# toshiba_board.net
KiCad netlist of a schematic drawn in EAGLE
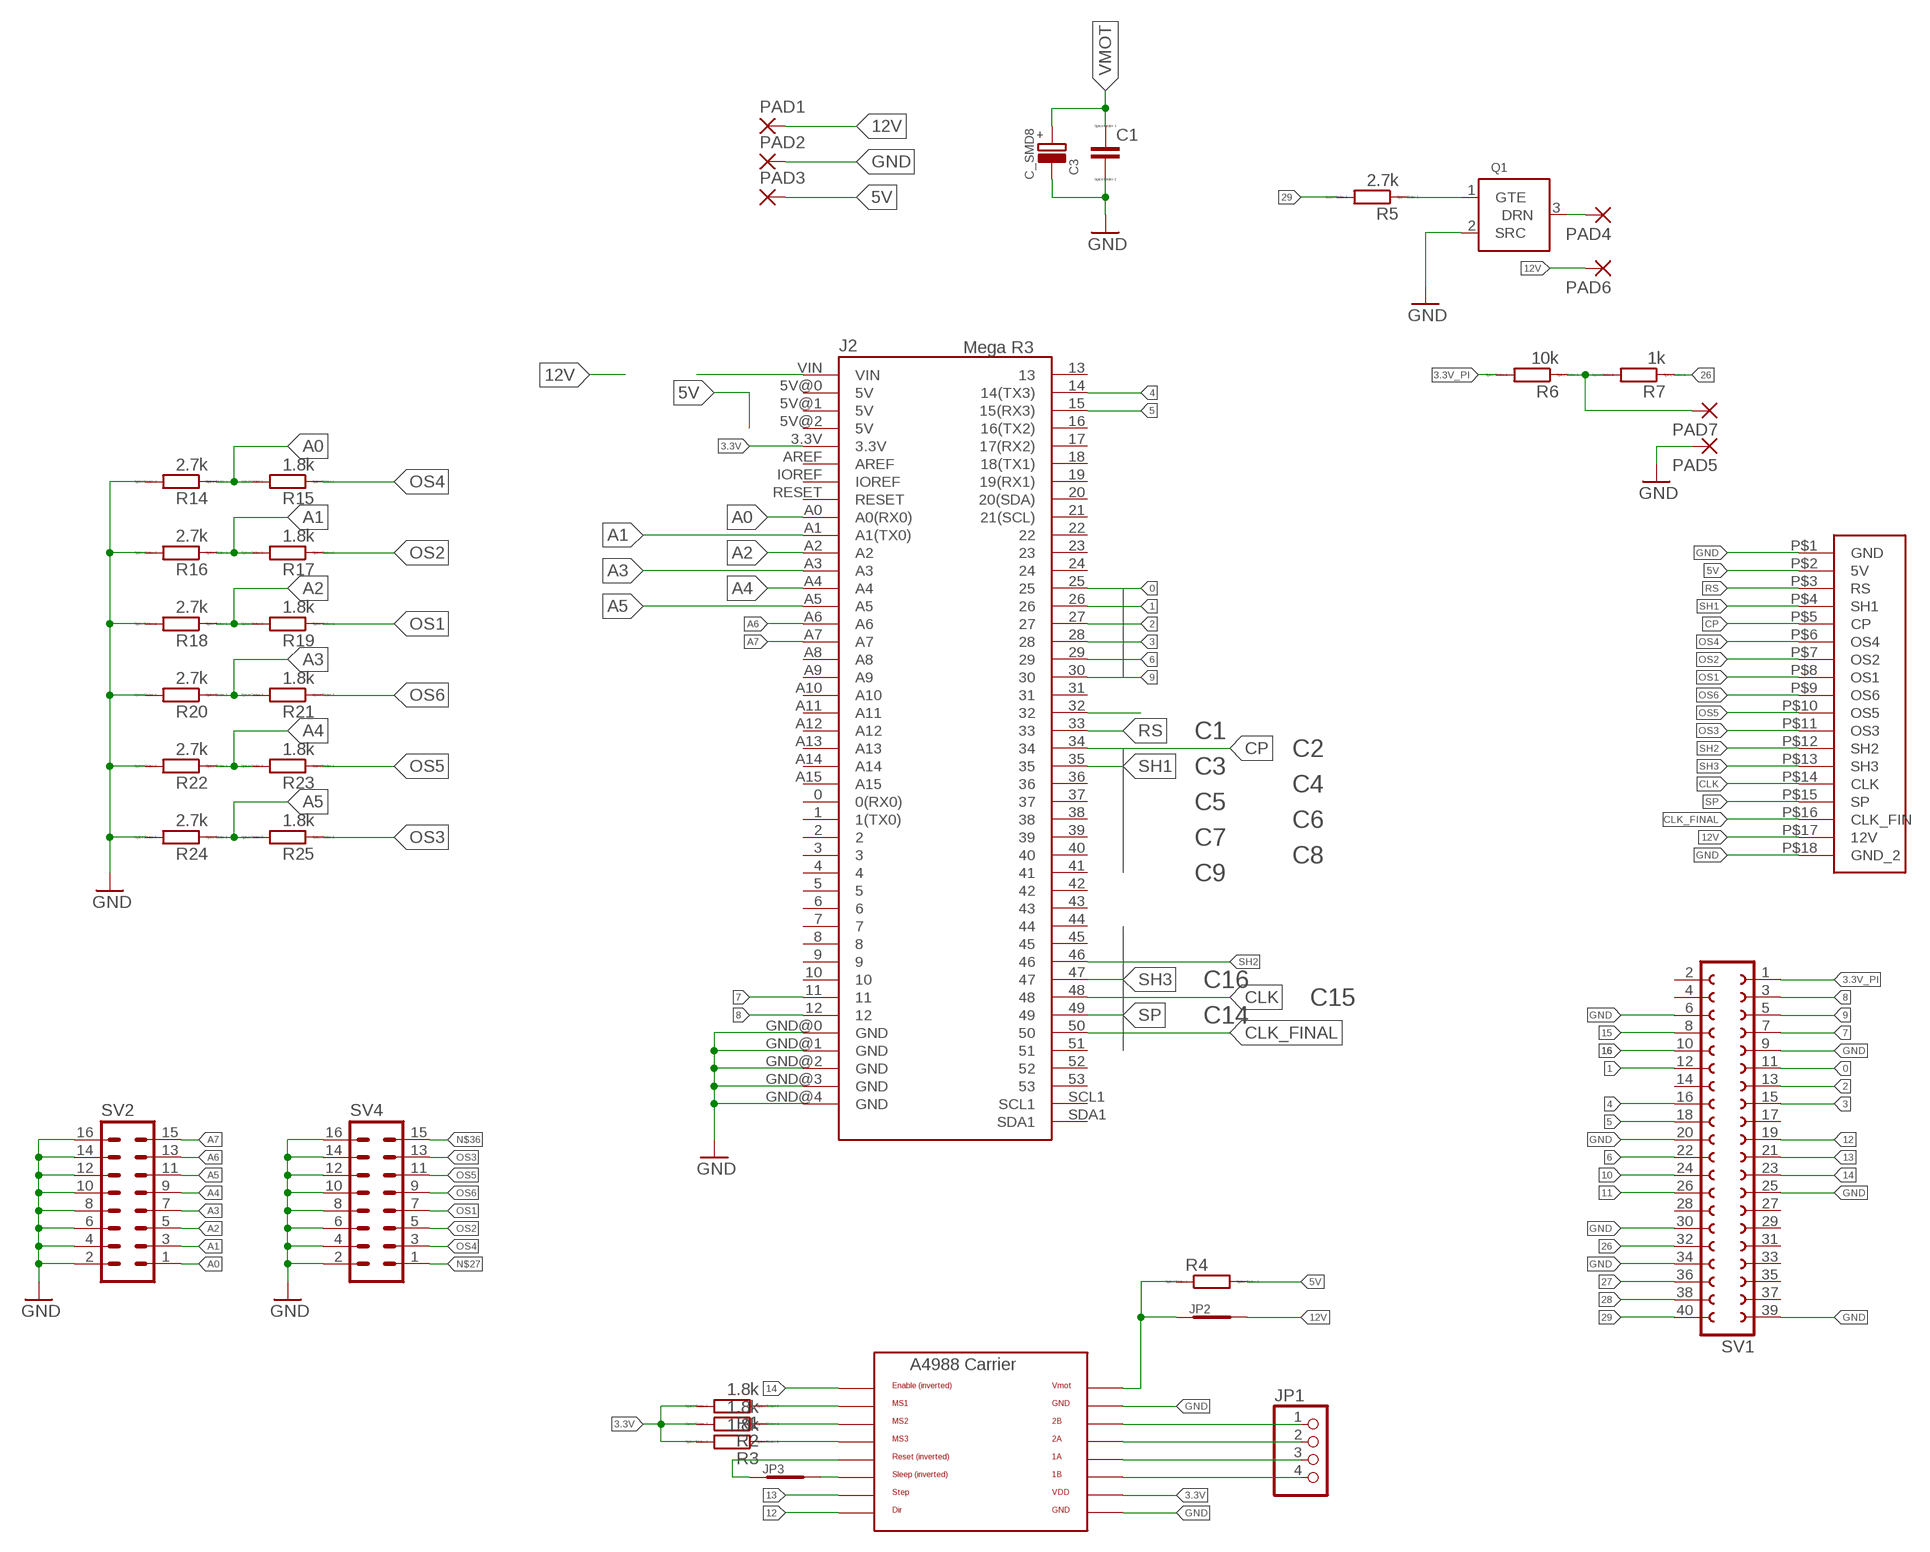
[diagram p0: schematic, sheet 1]

(export (version "E")
  (design (tool "Eeschema 10.0.6"))
  (components
    (comp (ref "C1")
      (value "C-EUC0805")
      (footprint "eagle-import:C0805")
      (libsource (lib "eagle-import") (part "C-EUC0805"))
    )
    (comp (ref "C3")
      (value "C_SMD8")
      (footprint "eagle-import:C-SMD-8MM")
      (libsource (lib "eagle-import") (part "C_SMD8"))
    )
    (comp (ref "J2")
      (value "Mega R3")
      (footprint "eagle-import:ARDUINO_MEGA")
      (libsource (lib "eagle-import") (part "ARDUINO-MEGAFULL"))
    )
    (comp (ref "JP1")
      (value "PINHD-1X4")
      (footprint "eagle-import:1X04")
      (libsource (lib "eagle-import") (part "PINHD-1X4"))
    )
    (comp (ref "JP2")
      (value "SHORT0805")
      (footprint "eagle-import:0805_SHORT")
      (libsource (lib "eagle-import") (part "SHORT0805"))
    )
    (comp (ref "JP3")
      (value "SHORT0805")
      (footprint "eagle-import:0805_SHORT")
      (libsource (lib "eagle-import") (part "SHORT0805"))
    )
    (comp (ref "PAD1")
      (value "SMD2")
      (footprint "eagle-import:SMD1,27-2,54")
      (libsource (lib "eagle-import") (part "SMD2"))
    )
    (comp (ref "PAD2")
      (value "SMD2")
      (footprint "eagle-import:SMD1,27-2,54")
      (libsource (lib "eagle-import") (part "SMD2"))
    )
    (comp (ref "PAD3")
      (value "SMD2")
      (footprint "eagle-import:SMD1,27-2,54")
      (libsource (lib "eagle-import") (part "SMD2"))
    )
    (comp (ref "PAD4")
      (value "SMD2")
      (footprint "eagle-import:SMD1,27-2,54")
      (libsource (lib "eagle-import") (part "SMD2"))
    )
    (comp (ref "PAD5")
      (value "SMD2")
      (footprint "eagle-import:SMD1,27-2,54")
      (libsource (lib "eagle-import") (part "SMD2"))
    )
    (comp (ref "PAD6")
      (value "SMD2")
      (footprint "eagle-import:SMD1,27-2,54")
      (libsource (lib "eagle-import") (part "SMD2"))
    )
    (comp (ref "PAD7")
      (value "SMD2")
      (footprint "eagle-import:SMD1,27-2,54")
      (libsource (lib "eagle-import") (part "SMD2"))
    )
    (comp (ref "Q1")
      (value "BSS138")
      (footprint "eagle-import:SOT23")
      (libsource (lib "eagle-import") (part "BSS138"))
    )
    (comp (ref "R1")
      (value "1.8k")
      (footprint "eagle-import:R0603")
      (libsource (lib "eagle-import") (part "R-EU_R0603"))
    )
    (comp (ref "R2")
      (value "1.8k")
      (footprint "eagle-import:R0603")
      (libsource (lib "eagle-import") (part "R-EU_R0603"))
    )
    (comp (ref "R3")
      (value "1.8k")
      (footprint "eagle-import:R0603")
      (libsource (lib "eagle-import") (part "R-EU_R0603"))
    )
    (comp (ref "R4")
      (value "R-EU_R0805")
      (footprint "eagle-import:R0805")
      (libsource (lib "eagle-import") (part "R-EU_R0805"))
    )
    (comp (ref "R5")
      (value "2.7k")
      (footprint "eagle-import:R0603")
      (libsource (lib "eagle-import") (part "R-EU_R0603"))
    )
    (comp (ref "R6")
      (value "10k")
      (footprint "eagle-import:R0603")
      (libsource (lib "eagle-import") (part "R-EU_R0603"))
    )
    (comp (ref "R7")
      (value "1k")
      (footprint "eagle-import:R0603")
      (libsource (lib "eagle-import") (part "R-EU_R0603"))
    )
    (comp (ref "R14")
      (value "2.7k")
      (footprint "eagle-import:R0603")
      (libsource (lib "eagle-import") (part "R-EU_R0603"))
    )
    (comp (ref "R15")
      (value "1.8k")
      (footprint "eagle-import:R0603")
      (libsource (lib "eagle-import") (part "R-EU_R0603"))
    )
    (comp (ref "R16")
      (value "2.7k")
      (footprint "eagle-import:R0603")
      (libsource (lib "eagle-import") (part "R-EU_R0603"))
    )
    (comp (ref "R17")
      (value "1.8k")
      (footprint "eagle-import:R0603")
      (libsource (lib "eagle-import") (part "R-EU_R0603"))
    )
    (comp (ref "R18")
      (value "2.7k")
      (footprint "eagle-import:R0603")
      (libsource (lib "eagle-import") (part "R-EU_R0603"))
    )
    (comp (ref "R19")
      (value "1.8k")
      (footprint "eagle-import:R0603")
      (libsource (lib "eagle-import") (part "R-EU_R0603"))
    )
    (comp (ref "R20")
      (value "2.7k")
      (footprint "eagle-import:R0603")
      (libsource (lib "eagle-import") (part "R-EU_R0603"))
    )
    (comp (ref "R21")
      (value "1.8k")
      (footprint "eagle-import:R0603")
      (libsource (lib "eagle-import") (part "R-EU_R0603"))
    )
    (comp (ref "R22")
      (value "2.7k")
      (footprint "eagle-import:R0603")
      (libsource (lib "eagle-import") (part "R-EU_R0603"))
    )
    (comp (ref "R23")
      (value "1.8k")
      (footprint "eagle-import:R0603")
      (libsource (lib "eagle-import") (part "R-EU_R0603"))
    )
    (comp (ref "R24")
      (value "2.7k")
      (footprint "eagle-import:R0603")
      (libsource (lib "eagle-import") (part "R-EU_R0603"))
    )
    (comp (ref "R25")
      (value "1.8k")
      (footprint "eagle-import:R0603")
      (libsource (lib "eagle-import") (part "R-EU_R0603"))
    )
    (comp (ref "SV1")
      (value "FE20-2")
      (footprint "eagle-import:FE20-2")
      (libsource (lib "eagle-import") (part "FE20-2"))
    )
    (comp (ref "SV2")
      (value "MA08-2")
      (footprint "eagle-import:MA08-2")
      (libsource (lib "eagle-import") (part "MA08-2"))
    )
    (comp (ref "SV4")
      (value "MA08-2")
      (footprint "eagle-import:MA08-2")
      (libsource (lib "eagle-import") (part "MA08-2"))
    )
    (comp (ref "U$1")
      (value "PIN_18")
      (footprint "eagle-import:PAD_18")
      (libsource (lib "eagle-import") (part "PIN_18"))
    )
    (comp (ref "U$2")
      (value "POLOLU_A4983CARRIER")
      (footprint "eagle-import:A4988BREAKOUT")
      (libsource (lib "eagle-import") (part "POLOLU_A4983CARRIER"))
    )
  )
  (nets
    (net (code "1") (name "0") (class "Default")
      (node (ref "J2") (pin "25") (pinfunction "25_25") (pintype "bidirectional"))
      (node (ref "SV1") (pin "11") (pinfunction "11_11") (pintype "passive"))
    )
    (net (code "2") (name "1") (class "Default")
      (node (ref "J2") (pin "26") (pinfunction "26_26") (pintype "bidirectional"))
      (node (ref "SV1") (pin "12") (pinfunction "12_12") (pintype "passive"))
    )
    (net (code "3") (name "2") (class "Default")
      (node (ref "J2") (pin "27") (pinfunction "27_27") (pintype "bidirectional"))
      (node (ref "SV1") (pin "13") (pinfunction "13_13") (pintype "passive"))
    )
    (net (code "4") (name "3") (class "Default")
      (node (ref "J2") (pin "28") (pinfunction "28_28") (pintype "bidirectional"))
      (node (ref "SV1") (pin "15") (pinfunction "15_15") (pintype "passive"))
    )
    (net (code "5") (name "3.3V") (class "Default")
      (node (ref "J2") (pin "3.3V") (pinfunction "3.3V_3.3V") (pintype "bidirectional"))
      (node (ref "R1") (pin "2") (pinfunction "2_2") (pintype "passive"))
      (node (ref "R2") (pin "2") (pinfunction "2_2") (pintype "passive"))
      (node (ref "R3") (pin "2") (pinfunction "2_2") (pintype "passive"))
      (node (ref "U$2") (pin "VDD") (pinfunction "VDD_VDD") (pintype "power_in"))
    )
    (net (code "6") (name "3.3V_PI") (class "Default")
      (node (ref "R6") (pin "2") (pinfunction "2_2") (pintype "passive"))
      (node (ref "SV1") (pin "1") (pinfunction "1_1") (pintype "passive"))
    )
    (net (code "7") (name "4") (class "Default")
      (node (ref "J2") (pin "14") (pinfunction "14(TX3)_14") (pintype "bidirectional"))
      (node (ref "SV1") (pin "16") (pinfunction "16_16") (pintype "passive"))
    )
    (net (code "8") (name "5") (class "Default")
      (node (ref "J2") (pin "15") (pinfunction "15(RX3)_15") (pintype "bidirectional"))
      (node (ref "SV1") (pin "18") (pinfunction "18_18") (pintype "passive"))
    )
    (net (code "9") (name "5V") (class "Default")
      (node (ref "PAD3") (pin "1") (pinfunction "P_1") (pintype "passive"))
      (node (ref "R4") (pin "2") (pinfunction "2_2") (pintype "passive"))
      (node (ref "U$1") (pin "P$2") (pinfunction "5V_P$2") (pintype "bidirectional"))
    )
    (net (code "10") (name "6") (class "Default")
      (node (ref "J2") (pin "29") (pinfunction "29_29") (pintype "bidirectional"))
      (node (ref "SV1") (pin "22") (pinfunction "22_22") (pintype "passive"))
    )
    (net (code "11") (name "7") (class "Default")
      (node (ref "J2") (pin "11") (pinfunction "11_11") (pintype "bidirectional"))
      (node (ref "SV1") (pin "7") (pinfunction "7_7") (pintype "passive"))
    )
    (net (code "12") (name "8") (class "Default")
      (node (ref "J2") (pin "12") (pinfunction "12_12") (pintype "bidirectional"))
      (node (ref "SV1") (pin "3") (pinfunction "3_3") (pintype "passive"))
    )
    (net (code "13") (name "9") (class "Default")
      (node (ref "J2") (pin "30") (pinfunction "30_30") (pintype "bidirectional"))
      (node (ref "SV1") (pin "5") (pinfunction "5_5") (pintype "passive"))
    )
    (net (code "14") (name "10") (class "Default")
      (node (ref "SV1") (pin "24") (pinfunction "24_24") (pintype "passive"))
    )
    (net (code "15") (name "11") (class "Default")
      (node (ref "SV1") (pin "26") (pinfunction "26_26") (pintype "passive"))
    )
    (net (code "16") (name "12") (class "Default")
      (node (ref "SV1") (pin "19") (pinfunction "19_19") (pintype "passive"))
      (node (ref "U$2") (pin "DIR") (pinfunction "DIR_DIR") (pintype "input"))
    )
    (net (code "17") (name "12V") (class "Default")
      (node (ref "JP2") (pin "P$2") (pinfunction "P$2_P$2") (pintype "bidirectional"))
      (node (ref "PAD1") (pin "1") (pinfunction "P_1") (pintype "passive"))
      (node (ref "PAD6") (pin "1") (pinfunction "P_1") (pintype "passive"))
      (node (ref "U$1") (pin "P$17") (pinfunction "12V_P$17") (pintype "bidirectional"))
    )
    (net (code "18") (name "13") (class "Default")
      (node (ref "SV1") (pin "21") (pinfunction "21_21") (pintype "passive"))
      (node (ref "U$2") (pin "STEP") (pinfunction "STEP_STEP") (pintype "input"))
    )
    (net (code "19") (name "14") (class "Default")
      (node (ref "SV1") (pin "23") (pinfunction "23_23") (pintype "passive"))
      (node (ref "U$2") (pin "EN") (pinfunction "EN_EN") (pintype "input"))
    )
    (net (code "20") (name "15") (class "Default")
      (node (ref "SV1") (pin "8") (pinfunction "8_8") (pintype "passive"))
    )
    (net (code "21") (name "16") (class "Default")
      (node (ref "SV1") (pin "10") (pinfunction "10_10") (pintype "passive"))
    )
    (net (code "22") (name "26") (class "Default")
      (node (ref "R7") (pin "1") (pinfunction "1_1") (pintype "passive"))
      (node (ref "SV1") (pin "32") (pinfunction "32_32") (pintype "passive"))
    )
    (net (code "23") (name "27") (class "Default")
      (node (ref "SV1") (pin "36") (pinfunction "36_36") (pintype "passive"))
    )
    (net (code "24") (name "28") (class "Default")
      (node (ref "SV1") (pin "38") (pinfunction "38_38") (pintype "passive"))
    )
    (net (code "25") (name "29") (class "Default")
      (node (ref "R5") (pin "2") (pinfunction "2_2") (pintype "passive"))
      (node (ref "SV1") (pin "40") (pinfunction "40_40") (pintype "passive"))
    )
    (net (code "26") (name "A0") (class "Default")
      (node (ref "J2") (pin "A0") (pinfunction "A0(RX0)_A0") (pintype "bidirectional"))
      (node (ref "R14") (pin "1") (pinfunction "1_1") (pintype "passive"))
      (node (ref "R15") (pin "2") (pinfunction "2_2") (pintype "passive"))
      (node (ref "SV2") (pin "1") (pinfunction "1_1") (pintype "passive"))
    )
    (net (code "27") (name "A1") (class "Default")
      (node (ref "J2") (pin "A1") (pinfunction "A1(TX0)_A1") (pintype "bidirectional"))
      (node (ref "R16") (pin "1") (pinfunction "1_1") (pintype "passive"))
      (node (ref "R17") (pin "2") (pinfunction "2_2") (pintype "passive"))
      (node (ref "SV2") (pin "3") (pinfunction "3_3") (pintype "passive"))
    )
    (net (code "28") (name "A2") (class "Default")
      (node (ref "J2") (pin "A2") (pinfunction "A2_A2") (pintype "bidirectional"))
      (node (ref "R18") (pin "1") (pinfunction "1_1") (pintype "passive"))
      (node (ref "R19") (pin "2") (pinfunction "2_2") (pintype "passive"))
      (node (ref "SV2") (pin "5") (pinfunction "5_5") (pintype "passive"))
    )
    (net (code "29") (name "A3") (class "Default")
      (node (ref "J2") (pin "A3") (pinfunction "A3_A3") (pintype "bidirectional"))
      (node (ref "R20") (pin "1") (pinfunction "1_1") (pintype "passive"))
      (node (ref "R21") (pin "2") (pinfunction "2_2") (pintype "passive"))
      (node (ref "SV2") (pin "7") (pinfunction "7_7") (pintype "passive"))
    )
    (net (code "30") (name "A4") (class "Default")
      (node (ref "J2") (pin "A4") (pinfunction "A4_A4") (pintype "bidirectional"))
      (node (ref "R22") (pin "1") (pinfunction "1_1") (pintype "passive"))
      (node (ref "R23") (pin "2") (pinfunction "2_2") (pintype "passive"))
      (node (ref "SV2") (pin "9") (pinfunction "9_9") (pintype "passive"))
    )
    (net (code "31") (name "A5") (class "Default")
      (node (ref "J2") (pin "A5") (pinfunction "A5_A5") (pintype "bidirectional"))
      (node (ref "R24") (pin "1") (pinfunction "1_1") (pintype "passive"))
      (node (ref "R25") (pin "2") (pinfunction "2_2") (pintype "passive"))
      (node (ref "SV2") (pin "11") (pinfunction "11_11") (pintype "passive"))
    )
    (net (code "32") (name "A6") (class "Default")
      (node (ref "J2") (pin "A6") (pinfunction "A6_A6") (pintype "bidirectional"))
      (node (ref "SV2") (pin "13") (pinfunction "13_13") (pintype "passive"))
    )
    (net (code "33") (name "A7") (class "Default")
      (node (ref "J2") (pin "A7") (pinfunction "A7_A7") (pintype "bidirectional"))
      (node (ref "SV2") (pin "15") (pinfunction "15_15") (pintype "passive"))
    )
    (net (code "34") (name "CLK") (class "Default")
      (node (ref "J2") (pin "48") (pinfunction "48_48") (pintype "bidirectional"))
      (node (ref "U$1") (pin "P$14") (pinfunction "CLK_P$14") (pintype "bidirectional"))
    )
    (net (code "35") (name "CLK_FINAL") (class "Default")
      (node (ref "J2") (pin "50") (pinfunction "50_50") (pintype "bidirectional"))
      (node (ref "U$1") (pin "P$16") (pinfunction "CLK_FIN_P$16") (pintype "bidirectional"))
    )
    (net (code "36") (name "CP") (class "Default")
      (node (ref "J2") (pin "34") (pinfunction "34_34") (pintype "bidirectional"))
      (node (ref "U$1") (pin "P$5") (pinfunction "CP_P$5") (pintype "bidirectional"))
    )
    (net (code "37") (name "GND") (class "Default")
      (node (ref "C1") (pin "2") (pinfunction "2_2") (pintype "passive"))
      (node (ref "C3") (pin "-") (pinfunction "-_-") (pintype "bidirectional"))
      (node (ref "J2") (pin "GND@0") (pinfunction "GND_GND@0") (pintype "bidirectional"))
      (node (ref "J2") (pin "GND@1") (pinfunction "GND_GND@1") (pintype "bidirectional"))
      (node (ref "J2") (pin "GND@2") (pinfunction "GND_GND@2") (pintype "bidirectional"))
      (node (ref "J2") (pin "GND@3") (pinfunction "GND_GND@3") (pintype "bidirectional"))
      (node (ref "J2") (pin "GND@4") (pinfunction "GND_GND@4") (pintype "bidirectional"))
      (node (ref "PAD2") (pin "1") (pinfunction "P_1") (pintype "passive"))
      (node (ref "PAD5") (pin "1") (pinfunction "P_1") (pintype "passive"))
      (node (ref "Q1") (pin "2") (pinfunction "SRC_2") (pintype "bidirectional"))
      (node (ref "R14") (pin "2") (pinfunction "2_2") (pintype "passive"))
      (node (ref "R16") (pin "2") (pinfunction "2_2") (pintype "passive"))
      (node (ref "R18") (pin "2") (pinfunction "2_2") (pintype "passive"))
      (node (ref "R20") (pin "2") (pinfunction "2_2") (pintype "passive"))
      (node (ref "R22") (pin "2") (pinfunction "2_2") (pintype "passive"))
      (node (ref "R24") (pin "2") (pinfunction "2_2") (pintype "passive"))
      (node (ref "SV1") (pin "20") (pinfunction "20_20") (pintype "passive"))
      (node (ref "SV1") (pin "25") (pinfunction "25_25") (pintype "passive"))
      (node (ref "SV1") (pin "30") (pinfunction "30_30") (pintype "passive"))
      (node (ref "SV1") (pin "34") (pinfunction "34_34") (pintype "passive"))
      (node (ref "SV1") (pin "39") (pinfunction "39_39") (pintype "passive"))
      (node (ref "SV1") (pin "6") (pinfunction "6_6") (pintype "passive"))
      (node (ref "SV1") (pin "9") (pinfunction "9_9") (pintype "passive"))
      (node (ref "SV2") (pin "10") (pinfunction "10_10") (pintype "passive"))
      (node (ref "SV2") (pin "12") (pinfunction "12_12") (pintype "passive"))
      (node (ref "SV2") (pin "14") (pinfunction "14_14") (pintype "passive"))
      (node (ref "SV2") (pin "16") (pinfunction "16_16") (pintype "passive"))
      (node (ref "SV2") (pin "2") (pinfunction "2_2") (pintype "passive"))
      (node (ref "SV2") (pin "4") (pinfunction "4_4") (pintype "passive"))
      (node (ref "SV2") (pin "6") (pinfunction "6_6") (pintype "passive"))
      (node (ref "SV2") (pin "8") (pinfunction "8_8") (pintype "passive"))
      (node (ref "SV4") (pin "10") (pinfunction "10_10") (pintype "passive"))
      (node (ref "SV4") (pin "12") (pinfunction "12_12") (pintype "passive"))
      (node (ref "SV4") (pin "14") (pinfunction "14_14") (pintype "passive"))
      (node (ref "SV4") (pin "16") (pinfunction "16_16") (pintype "passive"))
      (node (ref "SV4") (pin "2") (pinfunction "2_2") (pintype "passive"))
      (node (ref "SV4") (pin "4") (pinfunction "4_4") (pintype "passive"))
      (node (ref "SV4") (pin "6") (pinfunction "6_6") (pintype "passive"))
      (node (ref "SV4") (pin "8") (pinfunction "8_8") (pintype "passive"))
      (node (ref "U$1") (pin "P$1") (pinfunction "GND_P$1") (pintype "bidirectional"))
      (node (ref "U$1") (pin "P$18") (pinfunction "GND_2_P$18") (pintype "bidirectional"))
      (node (ref "U$2") (pin "GND") (pinfunction "GND_GND") (pintype "power_in"))
      (node (ref "U$2") (pin "GND@0") (pinfunction "GND_GND@0") (pintype "power_in"))
    )
    (net (code "38") (name "N$27") (class "Default")
      (node (ref "SV4") (pin "1") (pinfunction "1_1") (pintype "passive"))
    )
    (net (code "39") (name "N$36") (class "Default")
      (node (ref "SV4") (pin "15") (pinfunction "15_15") (pintype "passive"))
    )
    (net (code "40") (name "Net-(JP1-Pad1)") (class "Default")
      (node (ref "JP1") (pin "1") (pinfunction "1_1") (pintype "passive"))
      (node (ref "U$2") (pin "2B") (pinfunction "2B_2B") (pintype "output"))
    )
    (net (code "41") (name "Net-(JP1-Pad2)") (class "Default")
      (node (ref "JP1") (pin "2") (pinfunction "2_2") (pintype "passive"))
      (node (ref "U$2") (pin "2A") (pinfunction "2A_2A") (pintype "output"))
    )
    (net (code "42") (name "Net-(JP1-Pad3)") (class "Default")
      (node (ref "JP1") (pin "3") (pinfunction "3_3") (pintype "passive"))
      (node (ref "U$2") (pin "1A") (pinfunction "1A_1A") (pintype "output"))
    )
    (net (code "43") (name "Net-(JP1-Pad4)") (class "Default")
      (node (ref "JP1") (pin "4") (pinfunction "4_4") (pintype "passive"))
      (node (ref "U$2") (pin "1B") (pinfunction "1B_1B") (pintype "output"))
    )
    (net (code "44") (name "Net-(JP3-PadP$1)") (class "Default")
      (node (ref "JP3") (pin "P$1") (pinfunction "P$1_P$1") (pintype "bidirectional"))
      (node (ref "U$2") (pin "RST") (pinfunction "RST_RST") (pintype "input"))
    )
    (net (code "45") (name "Net-(PAD4-P)") (class "Default")
      (node (ref "PAD4") (pin "1") (pinfunction "P_1") (pintype "passive"))
      (node (ref "Q1") (pin "3") (pinfunction "DRN_3") (pintype "bidirectional"))
    )
    (net (code "46") (name "Net-(PAD7-P)") (class "Default")
      (node (ref "PAD7") (pin "1") (pinfunction "P_1") (pintype "passive"))
      (node (ref "R6") (pin "1") (pinfunction "1_1") (pintype "passive"))
      (node (ref "R7") (pin "2") (pinfunction "2_2") (pintype "passive"))
    )
    (net (code "47") (name "Net-(Q1-GTE)") (class "Default")
      (node (ref "Q1") (pin "1") (pinfunction "GTE_1") (pintype "bidirectional"))
      (node (ref "R5") (pin "1") (pinfunction "1_1") (pintype "passive"))
    )
    (net (code "48") (name "Net-(R1-Pad1)") (class "Default")
      (node (ref "R1") (pin "1") (pinfunction "1_1") (pintype "passive"))
      (node (ref "U$2") (pin "MS1") (pinfunction "MS1_MS1") (pintype "input"))
    )
    (net (code "49") (name "Net-(R2-Pad1)") (class "Default")
      (node (ref "R2") (pin "1") (pinfunction "1_1") (pintype "passive"))
      (node (ref "U$2") (pin "MS2") (pinfunction "MS2_MS2") (pintype "input"))
    )
    (net (code "50") (name "Net-(R3-Pad1)") (class "Default")
      (node (ref "R3") (pin "1") (pinfunction "1_1") (pintype "passive"))
      (node (ref "U$2") (pin "MS3") (pinfunction "MS3_MS3") (pintype "input"))
    )
    (net (code "51") (name "Net-(U$2-SLEEP)") (class "Default")
      (node (ref "JP3") (pin "P$2") (pinfunction "P$2_P$2") (pintype "bidirectional"))
      (node (ref "U$2") (pin "SLP") (pinfunction "SLEEP_SLP") (pintype "input"))
    )
    (net (code "52") (name "OS1") (class "Default")
      (node (ref "R19") (pin "1") (pinfunction "1_1") (pintype "passive"))
      (node (ref "SV4") (pin "7") (pinfunction "7_7") (pintype "passive"))
      (node (ref "U$1") (pin "P$8") (pinfunction "OS1_P$8") (pintype "bidirectional"))
    )
    (net (code "53") (name "OS2") (class "Default")
      (node (ref "R17") (pin "1") (pinfunction "1_1") (pintype "passive"))
      (node (ref "SV4") (pin "5") (pinfunction "5_5") (pintype "passive"))
      (node (ref "U$1") (pin "P$7") (pinfunction "OS2_P$7") (pintype "bidirectional"))
    )
    (net (code "54") (name "OS3") (class "Default")
      (node (ref "R25") (pin "1") (pinfunction "1_1") (pintype "passive"))
      (node (ref "SV4") (pin "13") (pinfunction "13_13") (pintype "passive"))
      (node (ref "U$1") (pin "P$11") (pinfunction "OS3_P$11") (pintype "bidirectional"))
    )
    (net (code "55") (name "OS4") (class "Default")
      (node (ref "R15") (pin "1") (pinfunction "1_1") (pintype "passive"))
      (node (ref "SV4") (pin "3") (pinfunction "3_3") (pintype "passive"))
      (node (ref "U$1") (pin "P$6") (pinfunction "OS4_P$6") (pintype "bidirectional"))
    )
    (net (code "56") (name "OS5") (class "Default")
      (node (ref "R23") (pin "1") (pinfunction "1_1") (pintype "passive"))
      (node (ref "SV4") (pin "11") (pinfunction "11_11") (pintype "passive"))
      (node (ref "U$1") (pin "P$10") (pinfunction "OS5_P$10") (pintype "bidirectional"))
    )
    (net (code "57") (name "OS6") (class "Default")
      (node (ref "R21") (pin "1") (pinfunction "1_1") (pintype "passive"))
      (node (ref "SV4") (pin "9") (pinfunction "9_9") (pintype "passive"))
      (node (ref "U$1") (pin "P$9") (pinfunction "OS6_P$9") (pintype "bidirectional"))
    )
    (net (code "58") (name "RS") (class "Default")
      (node (ref "J2") (pin "33") (pinfunction "33_33") (pintype "bidirectional"))
      (node (ref "U$1") (pin "P$3") (pinfunction "RS_P$3") (pintype "bidirectional"))
    )
    (net (code "59") (name "SH1") (class "Default")
      (node (ref "J2") (pin "35") (pinfunction "35_35") (pintype "bidirectional"))
      (node (ref "U$1") (pin "P$4") (pinfunction "SH1_P$4") (pintype "bidirectional"))
    )
    (net (code "60") (name "SH2") (class "Default")
      (node (ref "J2") (pin "46") (pinfunction "46_46") (pintype "bidirectional"))
      (node (ref "U$1") (pin "P$12") (pinfunction "SH2_P$12") (pintype "bidirectional"))
    )
    (net (code "61") (name "SH3") (class "Default")
      (node (ref "J2") (pin "47") (pinfunction "47_47") (pintype "bidirectional"))
      (node (ref "U$1") (pin "P$13") (pinfunction "SH3_P$13") (pintype "bidirectional"))
    )
    (net (code "62") (name "SP") (class "Default")
      (node (ref "J2") (pin "49") (pinfunction "49_49") (pintype "bidirectional"))
      (node (ref "U$1") (pin "P$15") (pinfunction "SP_P$15") (pintype "bidirectional"))
    )
    (net (code "63") (name "VMOT") (class "Default")
      (node (ref "C1") (pin "1") (pinfunction "1_1") (pintype "passive"))
      (node (ref "C3") (pin "+") (pinfunction "+_+") (pintype "bidirectional"))
      (node (ref "JP2") (pin "P$1") (pinfunction "P$1_P$1") (pintype "bidirectional"))
      (node (ref "R4") (pin "1") (pinfunction "1_1") (pintype "passive"))
      (node (ref "U$2") (pin "VMOT") (pinfunction "VMOT_VMOT") (pintype "power_in"))
    )
    (net (code "64") (name "unconnected-(J2-0(RX0)-Pad0)") (class "Default")
      (node (ref "J2") (pin "0") (pinfunction "0(RX0)_0") (pintype "bidirectional"))
    )
    (net (code "65") (name "unconnected-(J2-1(TX0)-Pad1)") (class "Default")
      (node (ref "J2") (pin "1") (pinfunction "1(TX0)_1") (pintype "bidirectional"))
    )
    (net (code "66") (name "unconnected-(J2-5V-Pad5V@0)") (class "Default")
      (node (ref "J2") (pin "5V@0") (pinfunction "5V_5V@0") (pintype "bidirectional"))
    )
    (net (code "67") (name "unconnected-(J2-5V-Pad5V@1)") (class "Default")
      (node (ref "J2") (pin "5V@1") (pinfunction "5V_5V@1") (pintype "bidirectional"))
    )
    (net (code "68") (name "unconnected-(J2-5V-Pad5V@2)") (class "Default")
      (node (ref "J2") (pin "5V@2") (pinfunction "5V_5V@2") (pintype "bidirectional"))
    )
    (net (code "69") (name "unconnected-(J2-16(TX2)-Pad16)") (class "Default")
      (node (ref "J2") (pin "16") (pinfunction "16(TX2)_16") (pintype "bidirectional"))
    )
    (net (code "70") (name "unconnected-(J2-17(RX2)-Pad17)") (class "Default")
      (node (ref "J2") (pin "17") (pinfunction "17(RX2)_17") (pintype "bidirectional"))
    )
    (net (code "71") (name "unconnected-(J2-18(TX1)-Pad18)") (class "Default")
      (node (ref "J2") (pin "18") (pinfunction "18(TX1)_18") (pintype "bidirectional"))
    )
    (net (code "72") (name "unconnected-(J2-19(RX1)-Pad19)") (class "Default")
      (node (ref "J2") (pin "19") (pinfunction "19(RX1)_19") (pintype "bidirectional"))
    )
    (net (code "73") (name "unconnected-(J2-20(SDA)-Pad20)") (class "Default")
      (node (ref "J2") (pin "20") (pinfunction "20(SDA)_20") (pintype "bidirectional"))
    )
    (net (code "74") (name "unconnected-(J2-21(SCL)-Pad21)") (class "Default")
      (node (ref "J2") (pin "21") (pinfunction "21(SCL)_21") (pintype "bidirectional"))
    )
    (net (code "75") (name "unconnected-(J2-Pad2)") (class "Default")
      (node (ref "J2") (pin "2") (pinfunction "2_2") (pintype "bidirectional"))
    )
    (net (code "76") (name "unconnected-(J2-Pad3)") (class "Default")
      (node (ref "J2") (pin "3") (pinfunction "3_3") (pintype "bidirectional"))
    )
    (net (code "77") (name "unconnected-(J2-Pad4)") (class "Default")
      (node (ref "J2") (pin "4") (pinfunction "4_4") (pintype "bidirectional"))
    )
    (net (code "78") (name "unconnected-(J2-Pad5)") (class "Default")
      (node (ref "J2") (pin "5") (pinfunction "5_5") (pintype "bidirectional"))
    )
    (net (code "79") (name "unconnected-(J2-Pad6)") (class "Default")
      (node (ref "J2") (pin "6") (pinfunction "6_6") (pintype "bidirectional"))
    )
    (net (code "80") (name "unconnected-(J2-Pad7)") (class "Default")
      (node (ref "J2") (pin "7") (pinfunction "7_7") (pintype "bidirectional"))
    )
    (net (code "81") (name "unconnected-(J2-Pad8)") (class "Default")
      (node (ref "J2") (pin "8") (pinfunction "8_8") (pintype "bidirectional"))
    )
    (net (code "82") (name "unconnected-(J2-Pad9)") (class "Default")
      (node (ref "J2") (pin "9") (pinfunction "9_9") (pintype "bidirectional"))
    )
    (net (code "83") (name "unconnected-(J2-Pad10)") (class "Default")
      (node (ref "J2") (pin "10") (pinfunction "10_10") (pintype "bidirectional"))
    )
    (net (code "84") (name "unconnected-(J2-Pad13)") (class "Default")
      (node (ref "J2") (pin "13") (pinfunction "13_13") (pintype "bidirectional"))
    )
    (net (code "85") (name "unconnected-(J2-Pad22)") (class "Default")
      (node (ref "J2") (pin "22") (pinfunction "22_22") (pintype "bidirectional"))
    )
    (net (code "86") (name "unconnected-(J2-Pad23)") (class "Default")
      (node (ref "J2") (pin "23") (pinfunction "23_23") (pintype "bidirectional"))
    )
    (net (code "87") (name "unconnected-(J2-Pad24)") (class "Default")
      (node (ref "J2") (pin "24") (pinfunction "24_24") (pintype "bidirectional"))
    )
    (net (code "88") (name "unconnected-(J2-Pad31)") (class "Default")
      (node (ref "J2") (pin "31") (pinfunction "31_31") (pintype "bidirectional"))
    )
    (net (code "89") (name "unconnected-(J2-Pad32)") (class "Default")
      (node (ref "J2") (pin "32") (pinfunction "32_32") (pintype "bidirectional"))
    )
    (net (code "90") (name "unconnected-(J2-Pad36)") (class "Default")
      (node (ref "J2") (pin "36") (pinfunction "36_36") (pintype "bidirectional"))
    )
    (net (code "91") (name "unconnected-(J2-Pad37)") (class "Default")
      (node (ref "J2") (pin "37") (pinfunction "37_37") (pintype "bidirectional"))
    )
    (net (code "92") (name "unconnected-(J2-Pad38)") (class "Default")
      (node (ref "J2") (pin "38") (pinfunction "38_38") (pintype "bidirectional"))
    )
    (net (code "93") (name "unconnected-(J2-Pad39)") (class "Default")
      (node (ref "J2") (pin "39") (pinfunction "39_39") (pintype "bidirectional"))
    )
    (net (code "94") (name "unconnected-(J2-Pad40)") (class "Default")
      (node (ref "J2") (pin "40") (pinfunction "40_40") (pintype "bidirectional"))
    )
    (net (code "95") (name "unconnected-(J2-Pad41)") (class "Default")
      (node (ref "J2") (pin "41") (pinfunction "41_41") (pintype "bidirectional"))
    )
    (net (code "96") (name "unconnected-(J2-Pad42)") (class "Default")
      (node (ref "J2") (pin "42") (pinfunction "42_42") (pintype "bidirectional"))
    )
    (net (code "97") (name "unconnected-(J2-Pad43)") (class "Default")
      (node (ref "J2") (pin "43") (pinfunction "43_43") (pintype "bidirectional"))
    )
    (net (code "98") (name "unconnected-(J2-Pad44)") (class "Default")
      (node (ref "J2") (pin "44") (pinfunction "44_44") (pintype "bidirectional"))
    )
    (net (code "99") (name "unconnected-(J2-Pad45)") (class "Default")
      (node (ref "J2") (pin "45") (pinfunction "45_45") (pintype "bidirectional"))
    )
    (net (code "100") (name "unconnected-(J2-Pad51)") (class "Default")
      (node (ref "J2") (pin "51") (pinfunction "51_51") (pintype "bidirectional"))
    )
    (net (code "101") (name "unconnected-(J2-Pad52)") (class "Default")
      (node (ref "J2") (pin "52") (pinfunction "52_52") (pintype "bidirectional"))
    )
    (net (code "102") (name "unconnected-(J2-Pad53)") (class "Default")
      (node (ref "J2") (pin "53") (pinfunction "53_53") (pintype "bidirectional"))
    )
    (net (code "103") (name "unconnected-(J2-PadA8)") (class "Default")
      (node (ref "J2") (pin "A8") (pinfunction "A8_A8") (pintype "bidirectional"))
    )
    (net (code "104") (name "unconnected-(J2-PadA9)") (class "Default")
      (node (ref "J2") (pin "A9") (pinfunction "A9_A9") (pintype "bidirectional"))
    )
    (net (code "105") (name "unconnected-(J2-PadA10)") (class "Default")
      (node (ref "J2") (pin "A10") (pinfunction "A10_A10") (pintype "bidirectional"))
    )
    (net (code "106") (name "unconnected-(J2-PadA11)") (class "Default")
      (node (ref "J2") (pin "A11") (pinfunction "A11_A11") (pintype "bidirectional"))
    )
    (net (code "107") (name "unconnected-(J2-PadA12)") (class "Default")
      (node (ref "J2") (pin "A12") (pinfunction "A12_A12") (pintype "bidirectional"))
    )
    (net (code "108") (name "unconnected-(J2-PadA13)") (class "Default")
      (node (ref "J2") (pin "A13") (pinfunction "A13_A13") (pintype "bidirectional"))
    )
    (net (code "109") (name "unconnected-(J2-PadA14)") (class "Default")
      (node (ref "J2") (pin "A14") (pinfunction "A14_A14") (pintype "bidirectional"))
    )
    (net (code "110") (name "unconnected-(J2-PadA15)") (class "Default")
      (node (ref "J2") (pin "A15") (pinfunction "A15_A15") (pintype "bidirectional"))
    )
    (net (code "111") (name "unconnected-(J2-PadAREF)") (class "Default")
      (node (ref "J2") (pin "AREF") (pinfunction "AREF_AREF") (pintype "bidirectional"))
    )
    (net (code "112") (name "unconnected-(J2-PadIOREF)") (class "Default")
      (node (ref "J2") (pin "IOREF") (pinfunction "IOREF_IOREF") (pintype "bidirectional"))
    )
    (net (code "113") (name "unconnected-(J2-PadRESET)") (class "Default")
      (node (ref "J2") (pin "RESET") (pinfunction "RESET_RESET") (pintype "bidirectional"))
    )
    (net (code "114") (name "unconnected-(J2-PadSCL1)") (class "Default")
      (node (ref "J2") (pin "SCL1") (pinfunction "SCL1_SCL1") (pintype "bidirectional"))
    )
    (net (code "115") (name "unconnected-(J2-PadSDA1)") (class "Default")
      (node (ref "J2") (pin "SDA1") (pinfunction "SDA1_SDA1") (pintype "bidirectional"))
    )
    (net (code "116") (name "unconnected-(J2-PadVIN)") (class "Default")
      (node (ref "J2") (pin "VIN") (pinfunction "VIN_VIN") (pintype "bidirectional"))
    )
    (net (code "117") (name "unconnected-(SV1-Pad2)") (class "Default")
      (node (ref "SV1") (pin "2") (pinfunction "2_2") (pintype "passive"))
    )
    (net (code "118") (name "unconnected-(SV1-Pad4)") (class "Default")
      (node (ref "SV1") (pin "4") (pinfunction "4_4") (pintype "passive"))
    )
    (net (code "119") (name "unconnected-(SV1-Pad14)") (class "Default")
      (node (ref "SV1") (pin "14") (pinfunction "14_14") (pintype "passive"))
    )
    (net (code "120") (name "unconnected-(SV1-Pad17)") (class "Default")
      (node (ref "SV1") (pin "17") (pinfunction "17_17") (pintype "passive"))
    )
    (net (code "121") (name "unconnected-(SV1-Pad27)") (class "Default")
      (node (ref "SV1") (pin "27") (pinfunction "27_27") (pintype "passive"))
    )
    (net (code "122") (name "unconnected-(SV1-Pad28)") (class "Default")
      (node (ref "SV1") (pin "28") (pinfunction "28_28") (pintype "passive"))
    )
    (net (code "123") (name "unconnected-(SV1-Pad29)") (class "Default")
      (node (ref "SV1") (pin "29") (pinfunction "29_29") (pintype "passive"))
    )
    (net (code "124") (name "unconnected-(SV1-Pad31)") (class "Default")
      (node (ref "SV1") (pin "31") (pinfunction "31_31") (pintype "passive"))
    )
    (net (code "125") (name "unconnected-(SV1-Pad33)") (class "Default")
      (node (ref "SV1") (pin "33") (pinfunction "33_33") (pintype "passive"))
    )
    (net (code "126") (name "unconnected-(SV1-Pad35)") (class "Default")
      (node (ref "SV1") (pin "35") (pinfunction "35_35") (pintype "passive"))
    )
    (net (code "127") (name "unconnected-(SV1-Pad37)") (class "Default")
      (node (ref "SV1") (pin "37") (pinfunction "37_37") (pintype "passive"))
    )
  )
)
